# Laser-Battle-IR-Sensor.net
KiCad netlist of a schematic drawn in EAGLE
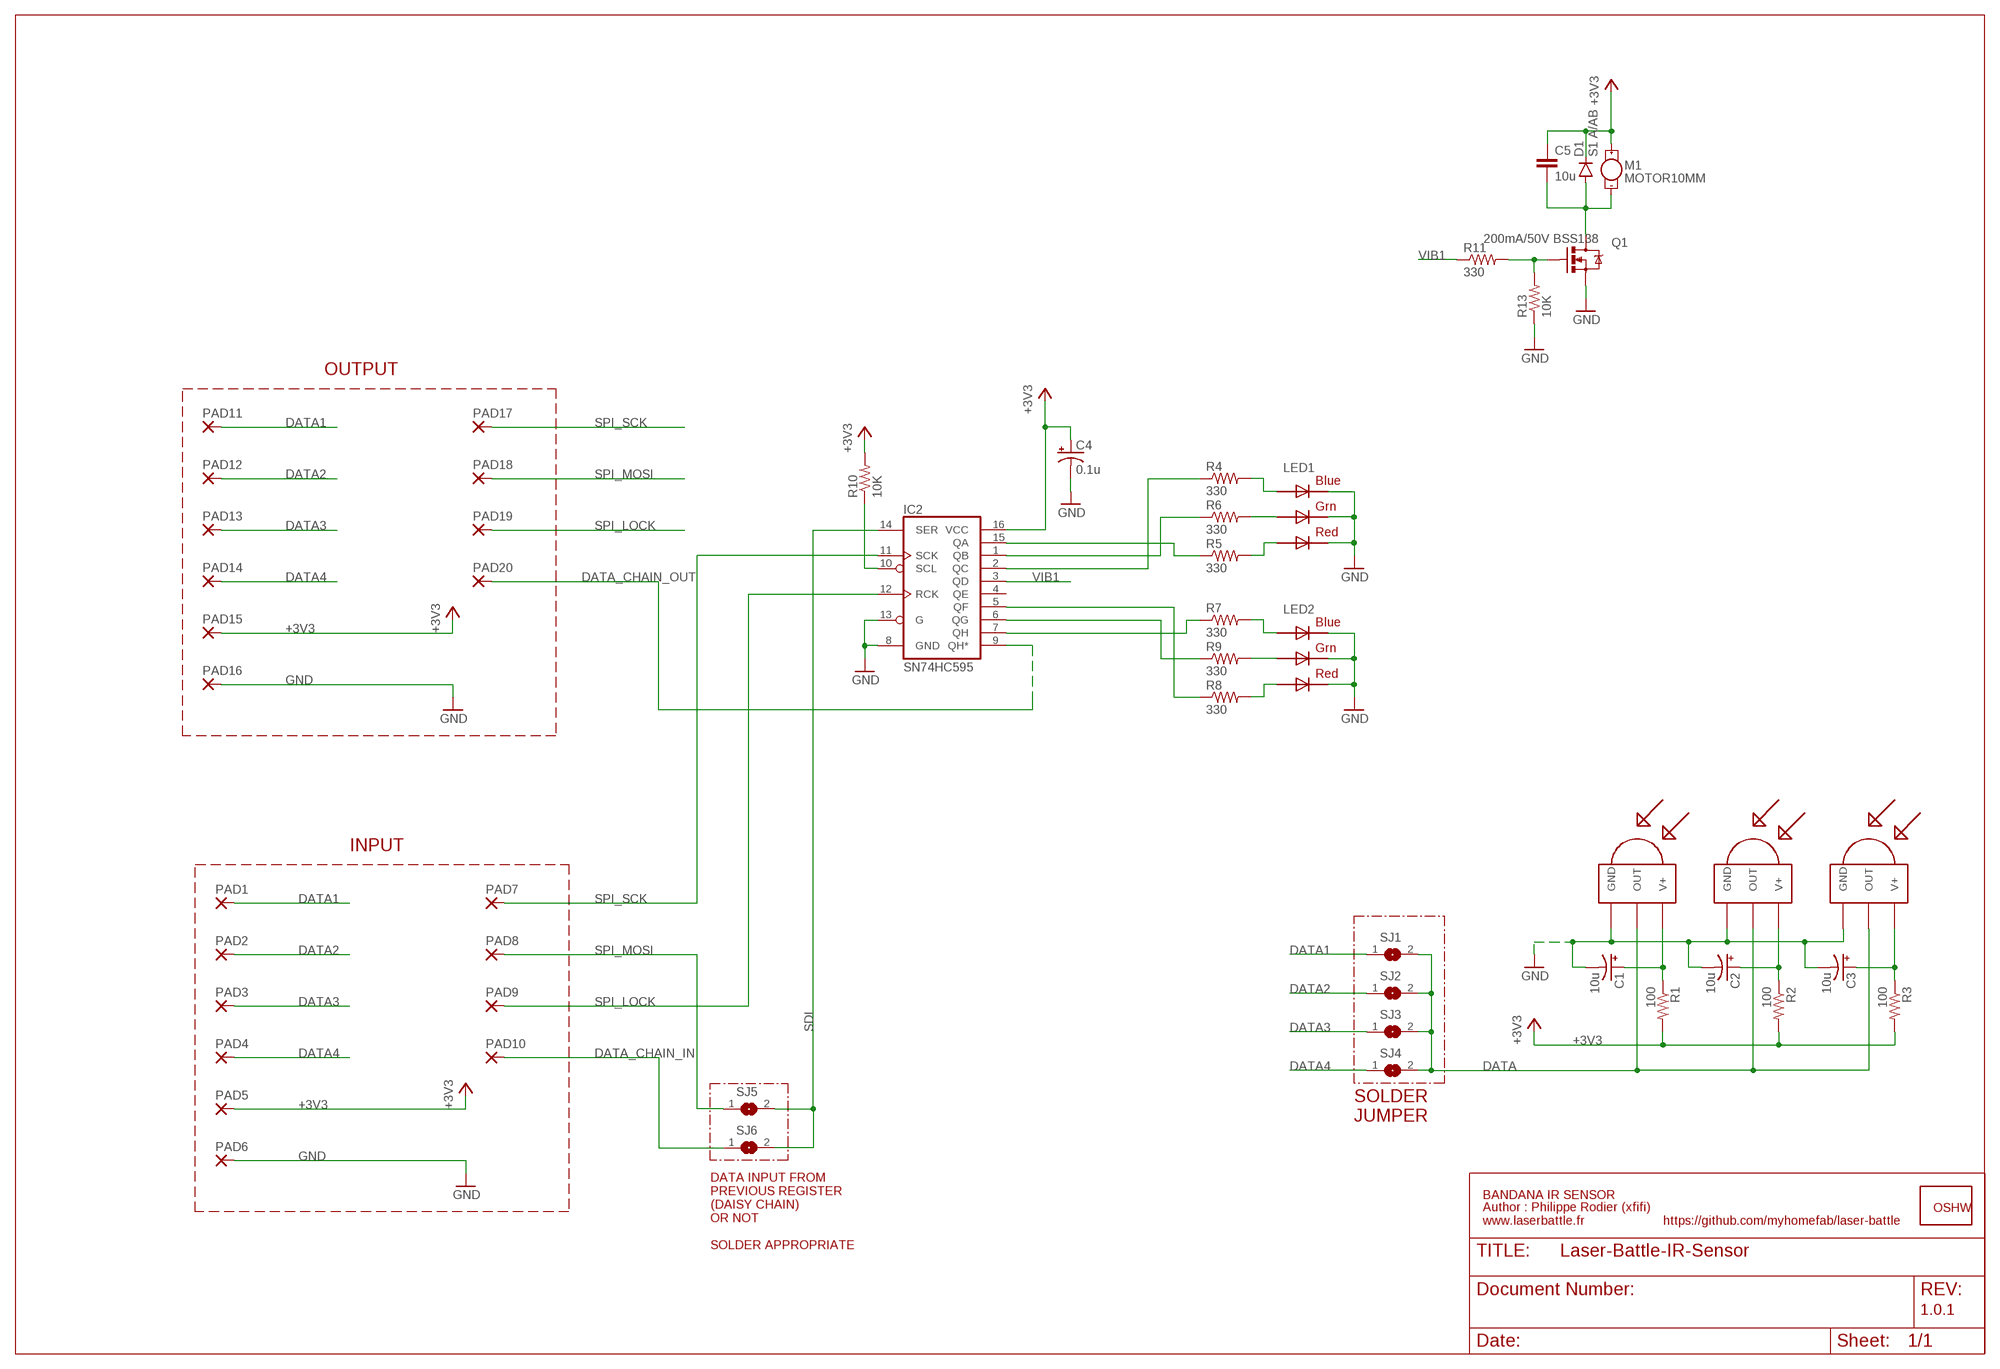
[diagram p0: schematic, sheet 1]

(export (version "E")
  (design (tool "Eeschema 10.0.6"))
  (components
    (comp (ref "C1")
      (value "10u")
      (footprint "eagle-import:EIA3216")
      (libsource (lib "eagle-import") (part "CAP_POL1206"))
    )
    (comp (ref "C2")
      (value "10u")
      (footprint "eagle-import:EIA3216")
      (libsource (lib "eagle-import") (part "CAP_POL1206"))
    )
    (comp (ref "C3")
      (value "10u")
      (footprint "eagle-import:EIA3216")
      (libsource (lib "eagle-import") (part "CAP_POL1206"))
    )
    (comp (ref "C4")
      (value "0.1u")
      (footprint "eagle-import:EIA3216")
      (libsource (lib "eagle-import") (part "CAP_POL1206"))
    )
    (comp (ref "C5")
      (value "10u")
      (footprint "eagle-import:0603-CAP")
      (libsource (lib "eagle-import") (part "CAP0603-CAP"))
    )
    (comp (ref "D1")
      (value "S1 A/AB")
      (footprint "eagle-import:SMA-DIODE")
      (libsource (lib "eagle-import") (part "DIODESMA"))
    )
    (comp (ref "GOLD_ORB_SM1")
      (value "OSHWLOGO_GOLD_ORB_SM")
      (footprint "eagle-import:OSHW2")
      (libsource (lib "eagle-import") (part "OSHWLOGO_GOLD_ORB_SM"))
    )
    (comp (ref "IC2")
      (value "SN74HC595")
      (footprint "eagle-import:TSSOP16")
      (libsource (lib "eagle-import") (part "74595"))
    )
    (comp (ref "IR1")
      (value "TSOP4856")
      (footprint "eagle-import:TSOP18XX")
      (libsource (lib "eagle-import") (part "TSOP4856"))
    )
    (comp (ref "IR2")
      (value "TSOP4856")
      (footprint "eagle-import:TSOP18XX")
      (libsource (lib "eagle-import") (part "TSOP4856"))
    )
    (comp (ref "IR3")
      (value "TSOP4856")
      (footprint "eagle-import:TSOP18XX")
      (libsource (lib "eagle-import") (part "TSOP4856"))
    )
    (comp (ref "LED1")
      (value "RGBLED5050")
      (footprint "eagle-import:RGBLED5050")
      (libsource (lib "eagle-import") (part "RGBLED5050"))
    )
    (comp (ref "LED2")
      (value "RGBLED5050")
      (footprint "eagle-import:RGBLED5050")
      (libsource (lib "eagle-import") (part "RGBLED5050"))
    )
    (comp (ref "M1")
      (value "MOTOR10MM")
      (footprint "eagle-import:VIBE-MOTOR-10MM")
      (libsource (lib "eagle-import") (part "MOTOR10MM"))
    )
    (comp (ref "PAD1")
      (value "1,6/0,8")
      (footprint "eagle-import:1,6_0,8")
      (libsource (lib "eagle-import") (part "1,6/0,8"))
    )
    (comp (ref "PAD2")
      (value "1,6/0,8")
      (footprint "eagle-import:1,6_0,8")
      (libsource (lib "eagle-import") (part "1,6/0,8"))
    )
    (comp (ref "PAD3")
      (value "1,6/0,8")
      (footprint "eagle-import:1,6_0,8")
      (libsource (lib "eagle-import") (part "1,6/0,8"))
    )
    (comp (ref "PAD4")
      (value "1,6/0,8")
      (footprint "eagle-import:1,6_0,8")
      (libsource (lib "eagle-import") (part "1,6/0,8"))
    )
    (comp (ref "PAD5")
      (value "1,6/0,8")
      (footprint "eagle-import:1,6_0,8")
      (libsource (lib "eagle-import") (part "1,6/0,8"))
    )
    (comp (ref "PAD6")
      (value "1,6/0,8")
      (footprint "eagle-import:1,6_0,8")
      (libsource (lib "eagle-import") (part "1,6/0,8"))
    )
    (comp (ref "PAD7")
      (value "1,6/0,8")
      (footprint "eagle-import:1,6_0,8")
      (libsource (lib "eagle-import") (part "1,6/0,8"))
    )
    (comp (ref "PAD8")
      (value "1,6/0,8")
      (footprint "eagle-import:1,6_0,8")
      (libsource (lib "eagle-import") (part "1,6/0,8"))
    )
    (comp (ref "PAD9")
      (value "1,6/0,8")
      (footprint "eagle-import:1,6_0,8")
      (libsource (lib "eagle-import") (part "1,6/0,8"))
    )
    (comp (ref "PAD10")
      (value "1,6/0,8")
      (footprint "eagle-import:1,6_0,8")
      (libsource (lib "eagle-import") (part "1,6/0,8"))
    )
    (comp (ref "PAD11")
      (value "1,6/0,8")
      (footprint "eagle-import:1,6_0,8")
      (libsource (lib "eagle-import") (part "1,6/0,8"))
    )
    (comp (ref "PAD12")
      (value "1,6/0,8")
      (footprint "eagle-import:1,6_0,8")
      (libsource (lib "eagle-import") (part "1,6/0,8"))
    )
    (comp (ref "PAD13")
      (value "1,6/0,8")
      (footprint "eagle-import:1,6_0,8")
      (libsource (lib "eagle-import") (part "1,6/0,8"))
    )
    (comp (ref "PAD14")
      (value "1,6/0,8")
      (footprint "eagle-import:1,6_0,8")
      (libsource (lib "eagle-import") (part "1,6/0,8"))
    )
    (comp (ref "PAD15")
      (value "1,6/0,8")
      (footprint "eagle-import:1,6_0,8")
      (libsource (lib "eagle-import") (part "1,6/0,8"))
    )
    (comp (ref "PAD16")
      (value "1,6/0,8")
      (footprint "eagle-import:1,6_0,8")
      (libsource (lib "eagle-import") (part "1,6/0,8"))
    )
    (comp (ref "PAD17")
      (value "1,6/0,8")
      (footprint "eagle-import:1,6_0,8")
      (libsource (lib "eagle-import") (part "1,6/0,8"))
    )
    (comp (ref "PAD18")
      (value "1,6/0,8")
      (footprint "eagle-import:1,6_0,8")
      (libsource (lib "eagle-import") (part "1,6/0,8"))
    )
    (comp (ref "PAD19")
      (value "1,6/0,8")
      (footprint "eagle-import:1,6_0,8")
      (libsource (lib "eagle-import") (part "1,6/0,8"))
    )
    (comp (ref "PAD20")
      (value "1,6/0,8")
      (footprint "eagle-import:1,6_0,8")
      (libsource (lib "eagle-import") (part "1,6/0,8"))
    )
    (comp (ref "Q1")
      (value "200mA/50V BSS138")
      (footprint "eagle-import:SOT23-3")
      (libsource (lib "eagle-import") (part "MOSFET-NCHANNELBSS138"))
    )
    (comp (ref "R1")
      (value "100")
      (footprint "eagle-import:0603-RES")
      (libsource (lib "eagle-import") (part "100OHM-1/10W-1%(0603)"))
    )
    (comp (ref "R2")
      (value "100")
      (footprint "eagle-import:0603-RES")
      (libsource (lib "eagle-import") (part "100OHM-1/10W-1%(0603)"))
    )
    (comp (ref "R3")
      (value "100")
      (footprint "eagle-import:0603-RES")
      (libsource (lib "eagle-import") (part "100OHM-1/10W-1%(0603)"))
    )
    (comp (ref "R4")
      (value "330")
      (footprint "eagle-import:0603-RES")
      (libsource (lib "eagle-import") (part "3.3KOHM1/10W1%(0603)"))
    )
    (comp (ref "R5")
      (value "330")
      (footprint "eagle-import:0603-RES")
      (libsource (lib "eagle-import") (part "3.3KOHM1/10W1%(0603)"))
    )
    (comp (ref "R6")
      (value "330")
      (footprint "eagle-import:0603-RES")
      (libsource (lib "eagle-import") (part "3.3KOHM1/10W1%(0603)"))
    )
    (comp (ref "R7")
      (value "330")
      (footprint "eagle-import:0603-RES")
      (libsource (lib "eagle-import") (part "3.3KOHM1/10W1%(0603)"))
    )
    (comp (ref "R8")
      (value "330")
      (footprint "eagle-import:0603-RES")
      (libsource (lib "eagle-import") (part "3.3KOHM1/10W1%(0603)"))
    )
    (comp (ref "R9")
      (value "330")
      (footprint "eagle-import:0603-RES")
      (libsource (lib "eagle-import") (part "3.3KOHM1/10W1%(0603)"))
    )
    (comp (ref "R10")
      (value "10K")
      (footprint "eagle-import:0603-RES")
      (libsource (lib "eagle-import") (part "10KOHM-1/10W-1%(0603)0603"))
    )
    (comp (ref "R11")
      (value "330")
      (footprint "eagle-import:0603-RES")
      (libsource (lib "eagle-import") (part "330OHM1/10W1%(0603)"))
    )
    (comp (ref "R13")
      (value "10K")
      (footprint "eagle-import:0603-RES")
      (libsource (lib "eagle-import") (part "10KOHM-1/10W-1%(0603)0603"))
    )
    (comp (ref "SJ1") (value "SJ") (footprint "eagle-import:SJ") (libsource (lib "eagle-import") (part "SJ")))
    (comp (ref "SJ2") (value "SJ") (footprint "eagle-import:SJ") (libsource (lib "eagle-import") (part "SJ")))
    (comp (ref "SJ3") (value "SJ") (footprint "eagle-import:SJ") (libsource (lib "eagle-import") (part "SJ")))
    (comp (ref "SJ4") (value "SJ") (footprint "eagle-import:SJ") (libsource (lib "eagle-import") (part "SJ")))
    (comp (ref "SJ5") (value "SJ") (footprint "eagle-import:SJ") (libsource (lib "eagle-import") (part "SJ")))
    (comp (ref "SJ6") (value "SJ") (footprint "eagle-import:SJ") (libsource (lib "eagle-import") (part "SJ")))
  )
  (nets
    (net (code "1") (name "+3V3") (class "Default")
      (node (ref "C4") (pin "A") (pinfunction "+_A") (pintype "passive"))
      (node (ref "C5") (pin "1") (pinfunction "1_1") (pintype "passive"))
      (node (ref "D1") (pin "C") (pinfunction "C_C") (pintype "passive"))
      (node (ref "IC2") (pin "16") (pinfunction "VCC_16") (pintype "power_in"))
      (node (ref "M1") (pin "+") (pinfunction "+_+") (pintype "bidirectional"))
      (node (ref "PAD15") (pin "1") (pinfunction "P_1") (pintype "passive"))
      (node (ref "PAD5") (pin "1") (pinfunction "P_1") (pintype "passive"))
      (node (ref "R1") (pin "2") (pinfunction "2_2") (pintype "passive"))
      (node (ref "R10") (pin "2") (pinfunction "2_2") (pintype "passive"))
      (node (ref "R2") (pin "2") (pinfunction "2_2") (pintype "passive"))
      (node (ref "R3") (pin "2") (pinfunction "2_2") (pintype "passive"))
    )
    (net (code "2") (name "/DATA") (class "Default")
      (node (ref "IR1") (pin "OUT") (pinfunction "OUT_OUT") (pintype "bidirectional"))
      (node (ref "IR2") (pin "OUT") (pinfunction "OUT_OUT") (pintype "bidirectional"))
      (node (ref "IR3") (pin "OUT") (pinfunction "OUT_OUT") (pintype "bidirectional"))
      (node (ref "SJ1") (pin "2") (pinfunction "2_2") (pintype "passive"))
      (node (ref "SJ2") (pin "2") (pinfunction "2_2") (pintype "passive"))
      (node (ref "SJ3") (pin "2") (pinfunction "2_2") (pintype "passive"))
      (node (ref "SJ4") (pin "2") (pinfunction "2_2") (pintype "passive"))
    )
    (net (code "3") (name "/DATA1") (class "Default")
      (node (ref "PAD1") (pin "1") (pinfunction "P_1") (pintype "passive"))
      (node (ref "PAD11") (pin "1") (pinfunction "P_1") (pintype "passive"))
      (node (ref "SJ1") (pin "1") (pinfunction "1_1") (pintype "passive"))
    )
    (net (code "4") (name "/DATA2") (class "Default")
      (node (ref "PAD12") (pin "1") (pinfunction "P_1") (pintype "passive"))
      (node (ref "PAD2") (pin "1") (pinfunction "P_1") (pintype "passive"))
      (node (ref "SJ2") (pin "1") (pinfunction "1_1") (pintype "passive"))
    )
    (net (code "5") (name "/DATA3") (class "Default")
      (node (ref "PAD13") (pin "1") (pinfunction "P_1") (pintype "passive"))
      (node (ref "PAD3") (pin "1") (pinfunction "P_1") (pintype "passive"))
      (node (ref "SJ3") (pin "1") (pinfunction "1_1") (pintype "passive"))
    )
    (net (code "6") (name "/DATA4") (class "Default")
      (node (ref "PAD14") (pin "1") (pinfunction "P_1") (pintype "passive"))
      (node (ref "PAD4") (pin "1") (pinfunction "P_1") (pintype "passive"))
      (node (ref "SJ4") (pin "1") (pinfunction "1_1") (pintype "passive"))
    )
    (net (code "7") (name "/DATA_CHAIN_IN") (class "Default")
      (node (ref "PAD10") (pin "1") (pinfunction "P_1") (pintype "passive"))
      (node (ref "SJ6") (pin "1") (pinfunction "1_1") (pintype "passive"))
    )
    (net (code "8") (name "/DATA_CHAIN_OUT") (class "Default")
      (node (ref "IC2") (pin "9") (pinfunction "QH*_9") (pintype "tri_state"))
      (node (ref "PAD20") (pin "1") (pinfunction "P_1") (pintype "passive"))
    )
    (net (code "9") (name "/SDI") (class "Default")
      (node (ref "IC2") (pin "14") (pinfunction "SER_14") (pintype "input"))
      (node (ref "SJ5") (pin "2") (pinfunction "2_2") (pintype "passive"))
      (node (ref "SJ6") (pin "2") (pinfunction "2_2") (pintype "passive"))
    )
    (net (code "10") (name "/SPI_LOCK") (class "Default")
      (node (ref "IC2") (pin "12") (pinfunction "RCK_12") (pintype "input"))
      (node (ref "PAD19") (pin "1") (pinfunction "P_1") (pintype "passive"))
      (node (ref "PAD9") (pin "1") (pinfunction "P_1") (pintype "passive"))
    )
    (net (code "11") (name "/SPI_MOSI") (class "Default")
      (node (ref "PAD18") (pin "1") (pinfunction "P_1") (pintype "passive"))
      (node (ref "PAD8") (pin "1") (pinfunction "P_1") (pintype "passive"))
      (node (ref "SJ5") (pin "1") (pinfunction "1_1") (pintype "passive"))
    )
    (net (code "12") (name "/SPI_SCK") (class "Default")
      (node (ref "IC2") (pin "11") (pinfunction "SCK_11") (pintype "input"))
      (node (ref "PAD17") (pin "1") (pinfunction "P_1") (pintype "passive"))
      (node (ref "PAD7") (pin "1") (pinfunction "P_1") (pintype "passive"))
    )
    (net (code "13") (name "/VIB1") (class "Default")
      (node (ref "IC2") (pin "3") (pinfunction "QD_3") (pintype "tri_state"))
      (node (ref "R11") (pin "1") (pinfunction "1_1") (pintype "passive"))
    )
    (net (code "14") (name "GND") (class "Default")
      (node (ref "C1") (pin "C") (pinfunction "-_C") (pintype "passive"))
      (node (ref "C2") (pin "C") (pinfunction "-_C") (pintype "passive"))
      (node (ref "C3") (pin "C") (pinfunction "-_C") (pintype "passive"))
      (node (ref "C4") (pin "C") (pinfunction "-_C") (pintype "passive"))
      (node (ref "IC2") (pin "13") (pinfunction "G_13") (pintype "input"))
      (node (ref "IC2") (pin "8") (pinfunction "GND_8") (pintype "power_in"))
      (node (ref "IR1") (pin "GND") (pinfunction "GND_GND") (pintype "bidirectional"))
      (node (ref "IR2") (pin "GND") (pinfunction "GND_GND") (pintype "bidirectional"))
      (node (ref "IR3") (pin "GND") (pinfunction "GND_GND") (pintype "bidirectional"))
      (node (ref "LED1") (pin "4") (pinfunction "BLUE_C_4") (pintype "bidirectional"))
      (node (ref "LED1") (pin "5") (pinfunction "RED_C_5") (pintype "bidirectional"))
      (node (ref "LED1") (pin "6") (pinfunction "GREEN_C_6") (pintype "bidirectional"))
      (node (ref "LED2") (pin "4") (pinfunction "BLUE_C_4") (pintype "bidirectional"))
      (node (ref "LED2") (pin "5") (pinfunction "RED_C_5") (pintype "bidirectional"))
      (node (ref "LED2") (pin "6") (pinfunction "GREEN_C_6") (pintype "bidirectional"))
      (node (ref "PAD16") (pin "1") (pinfunction "P_1") (pintype "passive"))
      (node (ref "PAD6") (pin "1") (pinfunction "P_1") (pintype "passive"))
      (node (ref "Q1") (pin "2") (pinfunction "S_2") (pintype "passive"))
      (node (ref "R13") (pin "1") (pinfunction "1_1") (pintype "passive"))
    )
    (net (code "15") (name "Net-(C1-+)") (class "Default")
      (node (ref "C1") (pin "A") (pinfunction "+_A") (pintype "passive"))
      (node (ref "IR1") (pin "VCC") (pinfunction "V+_VCC") (pintype "bidirectional"))
      (node (ref "R1") (pin "1") (pinfunction "1_1") (pintype "passive"))
    )
    (net (code "16") (name "Net-(C2-+)") (class "Default")
      (node (ref "C2") (pin "A") (pinfunction "+_A") (pintype "passive"))
      (node (ref "IR2") (pin "VCC") (pinfunction "V+_VCC") (pintype "bidirectional"))
      (node (ref "R2") (pin "1") (pinfunction "1_1") (pintype "passive"))
    )
    (net (code "17") (name "Net-(C3-+)") (class "Default")
      (node (ref "C3") (pin "A") (pinfunction "+_A") (pintype "passive"))
      (node (ref "IR3") (pin "VCC") (pinfunction "V+_VCC") (pintype "bidirectional"))
      (node (ref "R3") (pin "1") (pinfunction "1_1") (pintype "passive"))
    )
    (net (code "18") (name "Net-(IC2-QA)") (class "Default")
      (node (ref "IC2") (pin "15") (pinfunction "QA_15") (pintype "tri_state"))
      (node (ref "R5") (pin "1") (pinfunction "1_1") (pintype "passive"))
    )
    (net (code "19") (name "Net-(IC2-QB)") (class "Default")
      (node (ref "IC2") (pin "1") (pinfunction "QB_1") (pintype "tri_state"))
      (node (ref "R6") (pin "1") (pinfunction "1_1") (pintype "passive"))
    )
    (net (code "20") (name "Net-(IC2-QC)") (class "Default")
      (node (ref "IC2") (pin "2") (pinfunction "QC_2") (pintype "tri_state"))
      (node (ref "R4") (pin "1") (pinfunction "1_1") (pintype "passive"))
    )
    (net (code "21") (name "Net-(IC2-QF)") (class "Default")
      (node (ref "IC2") (pin "5") (pinfunction "QF_5") (pintype "tri_state"))
      (node (ref "R8") (pin "1") (pinfunction "1_1") (pintype "passive"))
    )
    (net (code "22") (name "Net-(IC2-QG)") (class "Default")
      (node (ref "IC2") (pin "6") (pinfunction "QG_6") (pintype "tri_state"))
      (node (ref "R9") (pin "1") (pinfunction "1_1") (pintype "passive"))
    )
    (net (code "23") (name "Net-(IC2-QH)") (class "Default")
      (node (ref "IC2") (pin "7") (pinfunction "QH_7") (pintype "tri_state"))
      (node (ref "R7") (pin "1") (pinfunction "1_1") (pintype "passive"))
    )
    (net (code "24") (name "Net-(IC2-SCL)") (class "Default")
      (node (ref "IC2") (pin "10") (pinfunction "SCL_10") (pintype "input"))
      (node (ref "R10") (pin "1") (pinfunction "1_1") (pintype "passive"))
    )
    (net (code "25") (name "Net-(LED1-BLUE_A)") (class "Default")
      (node (ref "LED1") (pin "3") (pinfunction "BLUE_A_3") (pintype "bidirectional"))
      (node (ref "R4") (pin "2") (pinfunction "2_2") (pintype "passive"))
    )
    (net (code "26") (name "Net-(LED1-GREEN_A)") (class "Default")
      (node (ref "LED1") (pin "1") (pinfunction "GREEN_A_1") (pintype "bidirectional"))
      (node (ref "R6") (pin "2") (pinfunction "2_2") (pintype "passive"))
    )
    (net (code "27") (name "Net-(LED1-RED_A)") (class "Default")
      (node (ref "LED1") (pin "2") (pinfunction "RED_A_2") (pintype "bidirectional"))
      (node (ref "R5") (pin "2") (pinfunction "2_2") (pintype "passive"))
    )
    (net (code "28") (name "Net-(LED2-BLUE_A)") (class "Default")
      (node (ref "LED2") (pin "3") (pinfunction "BLUE_A_3") (pintype "bidirectional"))
      (node (ref "R7") (pin "2") (pinfunction "2_2") (pintype "passive"))
    )
    (net (code "29") (name "Net-(LED2-GREEN_A)") (class "Default")
      (node (ref "LED2") (pin "1") (pinfunction "GREEN_A_1") (pintype "bidirectional"))
      (node (ref "R9") (pin "2") (pinfunction "2_2") (pintype "passive"))
    )
    (net (code "30") (name "Net-(LED2-RED_A)") (class "Default")
      (node (ref "LED2") (pin "2") (pinfunction "RED_A_2") (pintype "bidirectional"))
      (node (ref "R8") (pin "2") (pinfunction "2_2") (pintype "passive"))
    )
    (net (code "31") (name "Net-(Q1-D)") (class "Default")
      (node (ref "C5") (pin "2") (pinfunction "2_2") (pintype "passive"))
      (node (ref "D1") (pin "A") (pinfunction "A_A") (pintype "passive"))
      (node (ref "M1") (pin "-") (pinfunction "-_-") (pintype "bidirectional"))
      (node (ref "Q1") (pin "3") (pinfunction "D_3") (pintype "passive"))
    )
    (net (code "32") (name "Net-(Q1-G)") (class "Default")
      (node (ref "Q1") (pin "1") (pinfunction "G_1") (pintype "passive"))
      (node (ref "R11") (pin "2") (pinfunction "2_2") (pintype "passive"))
      (node (ref "R13") (pin "2") (pinfunction "2_2") (pintype "passive"))
    )
    (net (code "33") (name "unconnected-(IC2-QE-Pad4)") (class "Default")
      (node (ref "IC2") (pin "4") (pinfunction "QE_4") (pintype "tri_state"))
    )
  )
)
